# DM1097_PoE.net
KiCad netlist of a schematic drawn in Altium Designer
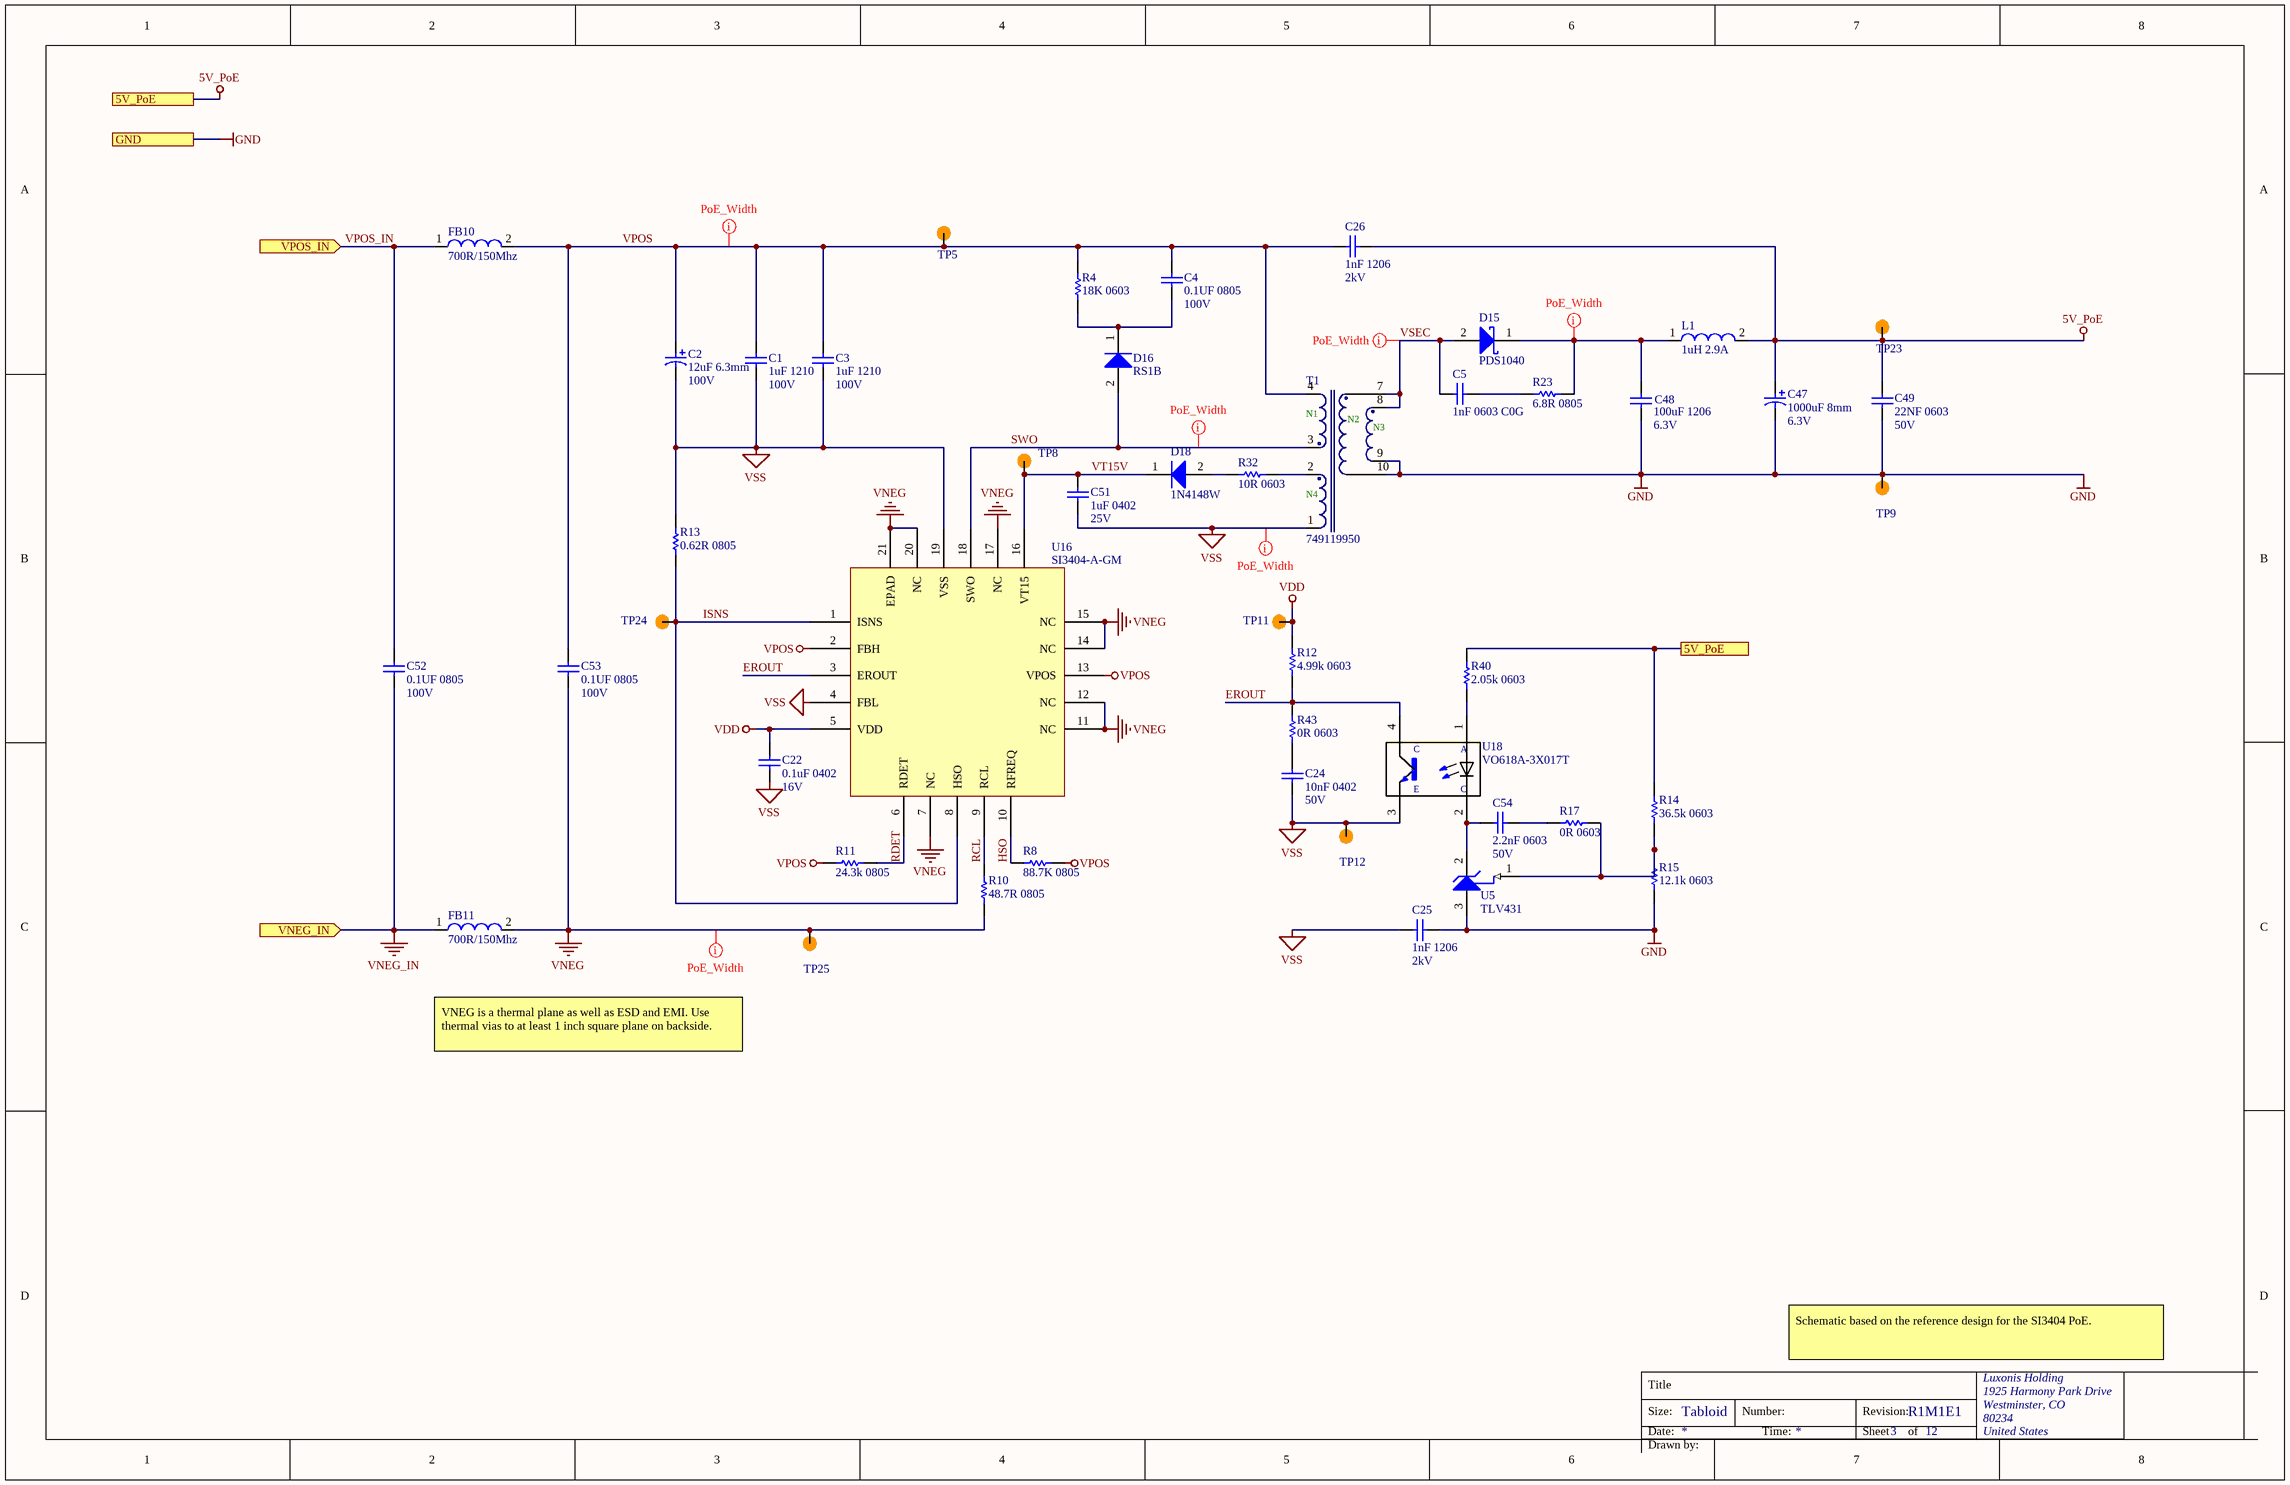
[diagram p0: DM1097_PoE.SchDoc]

(export (version "E")
  (design (tool "Eeschema 10.0.6"))
  (components
    (comp (ref "C1")
      (value "1uF 1210")
      (footprint "CAPC1210(3225)280_N")
      (description "CAP CER 1UF 100V X7R 1210")
      (fields (field (name "TOLERANCE") "10%") (field (name "VOLTAGE RATING") "100V"))
      (libsource (lib "PCBProject") (part "CL32B105KCJNNNE"))
    )
    (comp (ref "C2")
      (value "12uF 6.3mm")
      (footprint "EEU-FC2A120")
      (description "CAP ALUM 12UF 20% 100V RADIAL")
      (fields (field (name "TOLERANCE") "20%") (field (name "VOLTAGE") "100V"))
      (libsource (lib "BW2098POE") (part "EEU-FC2A120"))
    )
    (comp (ref "C3")
      (value "1uF 1210")
      (footprint "CAPC1210(3225)280_N")
      (description "CAP CER 1UF 100V X7R 1210")
      (fields (field (name "TOLERANCE") "10%") (field (name "VOLTAGE RATING") "100V"))
      (libsource (lib "PCBProject") (part "CL32B105KCJNNNE"))
    )
    (comp (ref "C4")
      (value "0.1UF 0805")
      (footprint "CAPC0805(2012)145_N")
      (description "CAP CER 0.1UF 100V X7R 0805")
      (fields (field (name "TOLERANCE") "10%") (field (name "VOLTAGE RATING") "100V"))
      (libsource (lib "BW2098POE") (part "CL21B104KCFNNNE"))
    )
    (comp (ref "C5")
      (value "1nF 0603 C0G")
      (footprint "CAP_Altium_Vault_Generic:CAPC0603(1608)100_N")
      (description "CAP CER 1000PF 50V C0G/NP0 0603")
      (fields
        (field (name "MANUFACTURER") "Murata")
        (field (name "MANUFACTURER PART NUMBER") "GRM1885C1H102FA01D")
      )
      (libsource (lib "LuxonisMaster") (part "GRM1885C1H102FA01D"))
    )
    (comp (ref "C22")
      (value "0.1uF 0402")
      (footprint "CAPC0402(1005)60_N")
      (description "CAP CER 0.1UF 16V X7R 0402")
      (fields (field (name "TOLERANCE") "10%") (field (name "VOLTAGE RATING") "16V"))
      (libsource (lib "PCBProject") (part "CL05B104KO5NFNC"))
    )
    (comp (ref "C24")
      (value "10nF 0402")
      (footprint "CAP_Altium_Vault_Generic:CAPC0402(1005)60_N")
      (description "CAP CER 10000PF 50V X7R 0402")
      (fields
        (field (name "TOLERANCE") "10%")
        (field (name "VOLTAGE") "25V")
        (field (name "VOLTAGE RATING") "50V")
      )
      (libsource (lib "LuxonisMaster") (part "GRM155R71H103KA88D"))
    )
    (comp (ref "C25")
      (value "1nF 1206")
      (footprint "CAPC1206(3216)190_N")
      (description "CAP CER 1000PF 2KV X7R 1206")
      (fields (field (name "TOLERANCE") "10%") (field (name "VOLTAGE RATING (DC)") "2kV"))
      (libsource (lib "PCBProject") (part "C1206C102KGRACTU"))
    )
    (comp (ref "C26")
      (value "1nF 1206")
      (footprint "CAPC1206(3216)190_N")
      (description "CAP CER 1000PF 2KV X7R 1206")
      (fields (field (name "TOLERANCE") "10%") (field (name "VOLTAGE RATING (DC)") "2kV"))
      (libsource (lib "PCBProject") (part "C1206C102KGRACTU"))
    )
    (comp (ref "C47")
      (value "1000uF 8mm")
      (footprint "ECA-0JM102")
      (description "CAP ALUM 1000UF 20% 6.3V RADIAL")
      (fields (field (name "TOLERANCE") "20%") (field (name "VOLTAGE") "6.3V"))
      (libsource (lib "BW2098POE") (part "ECA-0JM102"))
    )
    (comp (ref "C48")
      (value "100uF 1206")
      (footprint "CAPC1206(3216)190_N")
      (description "CAP CER 100UF 6.3V X5R 1206")
      (fields (field (name "TOLERANCE") "20%") (field (name "VOLTAGE") "6.3V"))
      (libsource (lib "PCBProject") (part "CL31A107MQHNNNE"))
    )
    (comp (ref "C49")
      (value "22NF 0603")
      (footprint "CAP_Altium_Vault_Generic:CAPC0603(1608)100_N")
      (description "CAP CER 0.022UF 50V X7R 0603")
      (fields (field (name "TOLERANCE") "10%") (field (name "VOLTAGE") "50V"))
      (libsource (lib "LuxonisMaster") (part "C0603C223K5RACTU"))
    )
    (comp (ref "C51")
      (value "1uF 0402")
      (footprint "CAP_Altium_Vault_Generic:CAPC0402(1005)70_N")
      (description "CAP CER 1UF 25V X5R 0402 10%")
      (fields
        (field (name "TOLERANCE") "10%")
        (field (name "VOLTAGE") "25V")
        (field (name "VOLTAGE RATING") "25V")
      )
      (libsource (lib "LuxonisMaster") (part "GRM155R61E105KA12D"))
    )
    (comp (ref "C52")
      (value "0.1UF 0805")
      (footprint "CAPC0805(2012)145_N")
      (description "CAP CER 0.1UF 100V X7R 0805")
      (fields (field (name "TOLERANCE") "10%") (field (name "VOLTAGE RATING") "100V"))
      (libsource (lib "PCBProject") (part "CL21B104KCFNNNE"))
    )
    (comp (ref "C53")
      (value "0.1UF 0805")
      (footprint "CAPC0805(2012)145_N")
      (description "CAP CER 0.1UF 100V X7R 0805")
      (fields (field (name "TOLERANCE") "10%") (field (name "VOLTAGE RATING") "100V"))
      (libsource (lib "PCBProject") (part "CL21B104KCFNNNE"))
    )
    (comp (ref "C54")
      (value "2.2nF 0603")
      (footprint "CAPC0603(1608)100_N")
      (description "CAP CER 2200PF 50V C0G/NP0 0603")
      (fields (field (name "TOLERANCE") "5%") (field (name "VOLTAGE") "50V"))
      (libsource (lib "BW2098POE") (part "GRM1885C1H222JA01D"))
    )
    (comp (ref "D15")
      (value "PDS1040")
      (footprint "PDS1040-13")
      (description "DIODE SCHOTTKY 40V 10A POWERDI5")
      (libsource (lib "PCBProject") (part "PDS1040-13"))
    )
    (comp (ref "D16")
      (value "RS1B")
      (footprint "RS1B")
      (description "DIODE GEN PURP 100V 1A SMA")
      (libsource (lib "BW2098POE") (part "RS1B"))
    )
    (comp (ref "D18")
      (value "1N4148W")
      (footprint "1N4148W-7-F")
      (description "DIODE GEN PURP 100V 300MA SOD123")
      (fields (field (name "VOLTAGE") "100V"))
      (libsource (lib "PCBProject") (part "1N4148W-7-F"))
    )
    (comp (ref "FB10")
      (value "700R/150Mhz")
      (footprint "742792040")
      (description "FERRITE BEAD 600 OHM 0805 1LN")
      (fields (field (name "TOLERANCE") "25%"))
      (libsource (lib "BW2098POE") (part "742792040"))
    )
    (comp (ref "FB11")
      (value "700R/150Mhz")
      (footprint "742792040")
      (description "FERRITE BEAD 600 OHM 0805 1LN")
      (fields (field (name "TOLERANCE") "25%"))
      (libsource (lib "BW2098POE") (part "742792040"))
    )
    (comp (ref "L1")
      (value "1uH 2.9A")
      (footprint "DO1608C-102MLx")
      (description "IND POWER WIREWOUND 1uH 20% 100KHz FERRITE 2.7A")
      (fields (field (name "TOLERANCE") "20%"))
      (libsource (lib "PCBProject") (part "DO1608C-102ML"))
    )
    (comp (ref "R4")
      (value "18K 0603")
      (footprint "RESC0603(1608)_N")
      (description "RES SMD 18K OHM 5% 1/10W 0603")
      (fields (field (name "TOLERANCE") "5%"))
      (libsource (lib "BW2098POE") (part "RC0603JR-0718KL"))
    )
    (comp (ref "R8")
      (value "88.7K 0805")
      (footprint "RESC0805(2012)_N")
      (description "RES SMD 88.7K OHM 1% 1/8W 0805")
      (fields (field (name "TOLERANCE") "1%"))
      (libsource (lib "BW2098POE") (part "CRCW080588K7FKEA"))
    )
    (comp (ref "R10")
      (value "48.7R 0805")
      (footprint "RESC0805(2012)_N")
      (description "RES SMD 48.7 OHM 1% 1/8W 0805")
      (fields (field (name "TOLERANCE") "1%"))
      (libsource (lib "PCBProject") (part "RC0805FR-0748R7L"))
    )
    (comp (ref "R11")
      (value "24.3k 0805")
      (footprint "RESC0805(2012)_N")
      (description "RES SMD 24.3K OHM 1% 1/8W 0805")
      (fields (field (name "TOLERANCE") "1%"))
      (libsource (lib "PCBProject") (part "CRCW080524K3FKEA"))
    )
    (comp (ref "R12")
      (value "4.99k 0603")
      (footprint "RESC0603(1608)_N")
      (description "RES SMD 4.99K OHM 1% 1/10W 0603")
      (fields (field (name "TOLERANCE") "1%"))
      (libsource (lib "PCBProject") (part "RC0603FR-074K99L"))
    )
    (comp (ref "R13")
      (value "0.62R 0805")
      (footprint "RESC0805(2012)_N")
      (description "RES SMD 620 MOHM 1% 1/8W 0805")
      (fields (field (name "TOLERANCE") "1%"))
      (libsource (lib "BW2098POE") (part "RL0805FR-070R62L"))
    )
    (comp (ref "R14")
      (value "36.5k 0603")
      (footprint "RESC0603(1608)_N")
      (description "RES SMD 36.5K OHM 1% 1/10W 0603")
      (fields (field (name "TOLERANCE") "1%"))
      (libsource (lib "PCBProject") (part "RC0603FR-0736K5L"))
    )
    (comp (ref "R15")
      (value "12.1k 0603")
      (footprint "RESC0603(1608)_N")
      (description "RES SMD 12.1K OHM 1% 1/10W 0603")
      (fields (field (name "TOLERANCE") "1%"))
      (libsource (lib "PCBProject") (part "RC0603FR-0712K1L"))
    )
    (comp (ref "R17")
      (value "0R 0603")
      (footprint "RES_Altium_Vault_Generic:RESC0603(1608)_N")
      (fields (field (name "TOLERANCE") "5%"))
      (libsource (lib "LuxonisMaster") (part "CRCW06030000Z0EA"))
    )
    (comp (ref "R23")
      (value "6.8R 0805")
      (footprint "RESC0805(2012)_N")
      (description "RES SMD 6.8 OHM 1% 1/8W 0805")
      (fields (field (name "TOLERANCE") "1%"))
      (libsource (lib "BW2098POE") (part "RC0805FR-076R8L"))
    )
    (comp (ref "R32")
      (value "10R 0603")
      (footprint "RESC0603(1608)_N")
      (description "RES SMD 10 OHM 1% 1/10W 0603")
      (fields (field (name "TOLERANCE") "1%"))
      (libsource (lib "PCBProject") (part "CRCW060310R0FKEA"))
    )
    (comp (ref "R40")
      (value "2.05k 0603")
      (footprint "RESC0603(1608)_N")
      (description "RES SMD 2.05K OHM 1% 1/10W 0603")
      (fields (field (name "TOLERANCE") "1%"))
      (libsource (lib "PCBProject") (part "RC0603FR-072K05L"))
    )
    (comp (ref "R43")
      (value "0R 0603")
      (footprint "RES_Altium_Vault_Generic:RESC0603(1608)_N")
      (fields (field (name "TOLERANCE") "5%"))
      (libsource (lib "LuxonisMaster") (part "CRCW06030000Z0EA"))
    )
    (comp (ref "T1")
      (value "749119950")
      (footprint "749119950")
      (description "TRANS FLYBACK POE 127UH SMD")
      (libsource (lib "BW2098POE") (part "749119950"))
    )
    (comp (ref "TP5")
      (value "TP100_200_NS")
      (footprint "LuxonisMaster:TP100_200_NS")
      (libsource (lib "LuxonisMaster") (part "TEST_POINT"))
    )
    (comp (ref "TP8")
      (value "TP100_200_NS")
      (footprint "LuxonisMaster:TP100_200_NS")
      (libsource (lib "LuxonisMaster") (part "TEST_POINT"))
    )
    (comp (ref "TP9")
      (value "TP100_200_NS")
      (footprint "LuxonisMaster:TP100_200_NS")
      (libsource (lib "LuxonisMaster") (part "TEST_POINT"))
    )
    (comp (ref "TP11")
      (value "TP100_200_NS")
      (footprint "LuxonisMaster:TP100_200_NS")
      (libsource (lib "LuxonisMaster") (part "TEST_POINT"))
    )
    (comp (ref "TP12")
      (value "TP100_200_NS")
      (footprint "LuxonisMaster:TP100_200_NS")
      (libsource (lib "LuxonisMaster") (part "TEST_POINT"))
    )
    (comp (ref "TP23")
      (value "TP100_200_NS")
      (footprint "LuxonisMaster:TP100_200_NS")
      (libsource (lib "LuxonisMaster") (part "TEST_POINT"))
    )
    (comp (ref "TP24")
      (value "TP100_200_NS")
      (footprint "LuxonisMaster:TP100_200_NS")
      (libsource (lib "LuxonisMaster") (part "TEST_POINT"))
    )
    (comp (ref "TP25")
      (value "TP100_200_NS")
      (footprint "LuxonisMaster:TP100_200_NS")
      (libsource (lib "LuxonisMaster") (part "TEST_POINT"))
    )
    (comp (ref "U5")
      (value "TLV431")
      (footprint "TLV431BCDBZR")
      (description "IC VREF SHUNT ADJ SOT23-3")
      (fields (field (name "TOLERANCE") "0.5%"))
      (libsource (lib "BW2098POE") (part "TLV431BCDBZR"))
    )
    (comp (ref "U16")
      (value "SI3404-A-GM")
      (footprint "Si3404-A-GM")
      (description "IC POE CNTRL 1 CHANNEL 20QFN")
      (libsource (lib "BW2098POE") (part "SI3404-A-GM"))
    )
    (comp (ref "U18")
      (value "VO618A-3X017T")
      (footprint "VO618A-3X017T")
      (description "OPTOISOLATOR 5.3KV TRANS 4-SMD")
      (libsource (lib "BW2098POE") (part "VO618A-3X017T"))
    )
  )
  (nets
    (net (code "1") (name "/EROUT") (class "Default")
      (node (ref "R12") (pin "1") (pinfunction "1_1") (pintype "passive"))
      (node (ref "R43") (pin "2") (pinfunction "2_2") (pintype "passive"))
      (node (ref "U16") (pin "3") (pinfunction "EROUT_3") (pintype "passive"))
      (node (ref "U18") (pin "4") (pinfunction "CO_4") (pintype "passive"))
    )
    (net (code "2") (name "/HSO") (class "Default")
      (node (ref "R8") (pin "2") (pinfunction "2_2") (pintype "passive"))
      (node (ref "U16") (pin "10") (pinfunction "RFREQ_10") (pintype "passive"))
    )
    (net (code "3") (name "/ISNS") (class "Default")
      (node (ref "R13") (pin "1") (pinfunction "1_1") (pintype "passive"))
      (node (ref "TP24") (pin "1") (pintype "passive"))
      (node (ref "U16") (pin "1") (pinfunction "ISNS_1") (pintype "passive"))
      (node (ref "U16") (pin "8") (pinfunction "HSO_8") (pintype "passive"))
    )
    (net (code "4") (name "/RCL") (class "Default")
      (node (ref "R10") (pin "2") (pinfunction "2_2") (pintype "passive"))
      (node (ref "U16") (pin "9") (pinfunction "RCL_9") (pintype "passive"))
    )
    (net (code "5") (name "/RDET") (class "Default")
      (node (ref "R11") (pin "1") (pinfunction "1_1") (pintype "passive"))
      (node (ref "U16") (pin "6") (pinfunction "RDET_6") (pintype "passive"))
    )
    (net (code "6") (name "/SWO") (class "Default")
      (node (ref "D16") (pin "2") (pinfunction "A_2") (pintype "passive"))
      (node (ref "T1") (pin "3") (pinfunction "3_3") (pintype "passive"))
      (node (ref "U16") (pin "18") (pinfunction "SWO_18") (pintype "passive"))
    )
    (net (code "7") (name "/VPOS_IN") (class "Default")
      (node (ref "C52") (pin "2") (pinfunction "2_2") (pintype "passive"))
      (node (ref "FB10") (pin "1") (pinfunction "1_1") (pintype "passive"))
    )
    (net (code "8") (name "/VSEC") (class "Default")
      (node (ref "C5") (pin "2") (pinfunction "2_2") (pintype "passive"))
      (node (ref "D15") (pin "2") (pinfunction "A_2") (pintype "passive"))
      (node (ref "T1") (pin "7") (pinfunction "7_7") (pintype "passive"))
      (node (ref "T1") (pin "8") (pinfunction "8_8") (pintype "passive"))
    )
    (net (code "9") (name "/VT15V") (class "Default")
      (node (ref "C51") (pin "2") (pinfunction "2_2") (pintype "passive"))
      (node (ref "D18") (pin "1") (pinfunction "K_1") (pintype "passive"))
      (node (ref "TP8") (pin "1") (pintype "passive"))
      (node (ref "U16") (pin "16") (pinfunction "VT15_16") (pintype "passive"))
    )
    (net (code "10") (name "5V_PoE") (class "Default")
      (node (ref "C26") (pin "2") (pinfunction "2_2") (pintype "passive"))
      (node (ref "C47") (pin "1") (pinfunction "1_1") (pintype "passive"))
      (node (ref "C49") (pin "2") (pinfunction "2_2") (pintype "passive"))
      (node (ref "L1") (pin "2") (pinfunction "2_2") (pintype "passive"))
      (node (ref "R14") (pin "2") (pinfunction "2_2") (pintype "passive"))
      (node (ref "R40") (pin "2") (pinfunction "2_2") (pintype "passive"))
      (node (ref "TP23") (pin "1") (pintype "passive"))
    )
    (net (code "11") (name "GND") (class "Default")
      (node (ref "C25") (pin "2") (pinfunction "2_2") (pintype "passive"))
      (node (ref "C47") (pin "2") (pinfunction "2_2") (pintype "passive"))
      (node (ref "C48") (pin "1") (pinfunction "1_1") (pintype "passive"))
      (node (ref "C49") (pin "1") (pinfunction "1_1") (pintype "passive"))
      (node (ref "R15") (pin "1") (pinfunction "1_1") (pintype "passive"))
      (node (ref "T1") (pin "10") (pinfunction "10_10") (pintype "passive"))
      (node (ref "T1") (pin "9") (pinfunction "9_9") (pintype "passive"))
      (node (ref "TP9") (pin "1") (pintype "passive"))
      (node (ref "U5") (pin "3") (pinfunction "ANODE_3") (pintype "passive"))
    )
    (net (code "12") (name "Net-(C5-Pad1)") (class "Default")
      (node (ref "C5") (pin "1") (pinfunction "1_1") (pintype "passive"))
      (node (ref "R23") (pin "1") (pinfunction "1_1") (pintype "passive"))
    )
    (net (code "13") (name "Net-(C24-Pad2)") (class "Default")
      (node (ref "C24") (pin "2") (pinfunction "2_2") (pintype "passive"))
      (node (ref "R43") (pin "1") (pinfunction "1_1") (pintype "passive"))
    )
    (net (code "14") (name "Net-(C54-Pad2)") (class "Default")
      (node (ref "C54") (pin "2") (pinfunction "2_2") (pintype "passive"))
      (node (ref "R17") (pin "2") (pinfunction "2_2") (pintype "passive"))
    )
    (net (code "15") (name "Net-(D15-K)") (class "Default")
      (node (ref "C48") (pin "2") (pinfunction "2_2") (pintype "passive"))
      (node (ref "D15") (pin "1") (pinfunction "K_1") (pintype "passive"))
      (node (ref "L1") (pin "1") (pinfunction "1_1") (pintype "passive"))
      (node (ref "R23") (pin "2") (pinfunction "2_2") (pintype "passive"))
    )
    (net (code "16") (name "Net-(D16-K)") (class "Default")
      (node (ref "C4") (pin "1") (pinfunction "1_1") (pintype "passive"))
      (node (ref "D16") (pin "1") (pinfunction "K_1") (pintype "passive"))
      (node (ref "R4") (pin "1") (pinfunction "1_1") (pintype "passive"))
    )
    (net (code "17") (name "Net-(D18-A)") (class "Default")
      (node (ref "D18") (pin "2") (pinfunction "A_2") (pintype "passive"))
      (node (ref "R32") (pin "1") (pinfunction "1_1") (pintype "passive"))
    )
    (net (code "18") (name "Net-(R32-Pad2)") (class "Default")
      (node (ref "R32") (pin "2") (pinfunction "2_2") (pintype "passive"))
      (node (ref "T1") (pin "2") (pinfunction "2_2") (pintype "passive"))
    )
    (net (code "19") (name "Net-(U5-REF)") (class "Default")
      (node (ref "R14") (pin "1") (pinfunction "1_1") (pintype "passive"))
      (node (ref "R15") (pin "2") (pinfunction "2_2") (pintype "passive"))
      (node (ref "R17") (pin "1") (pinfunction "1_1") (pintype "passive"))
      (node (ref "U5") (pin "1") (pinfunction "REF_1") (pintype "input"))
    )
    (net (code "20") (name "Net-(U18-A)") (class "Default")
      (node (ref "R40") (pin "1") (pinfunction "1_1") (pintype "passive"))
      (node (ref "U18") (pin "1") (pinfunction "A_1") (pintype "passive"))
    )
    (net (code "21") (name "Net-(U18-C)") (class "Default")
      (node (ref "C54") (pin "1") (pinfunction "1_1") (pintype "passive"))
      (node (ref "U18") (pin "2") (pinfunction "C_2") (pintype "passive"))
      (node (ref "U5") (pin "2") (pinfunction "CATHODE_2") (pintype "passive"))
    )
    (net (code "22") (name "VDD") (class "Default")
      (node (ref "C22") (pin "2") (pinfunction "2_2") (pintype "passive"))
      (node (ref "R12") (pin "2") (pinfunction "2_2") (pintype "passive"))
      (node (ref "TP11") (pin "1") (pintype "passive"))
      (node (ref "U16") (pin "5") (pinfunction "VDD_5") (pintype "passive"))
    )
    (net (code "23") (name "VNEG") (class "Default")
      (node (ref "C53") (pin "1") (pinfunction "1_1") (pintype "passive"))
      (node (ref "FB11") (pin "2") (pinfunction "2_2") (pintype "passive"))
      (node (ref "R10") (pin "1") (pinfunction "1_1") (pintype "passive"))
      (node (ref "TP25") (pin "1") (pintype "passive"))
      (node (ref "U16") (pin "11") (pinfunction "NC_11") (pintype "passive"))
      (node (ref "U16") (pin "12") (pinfunction "NC_12") (pintype "passive"))
      (node (ref "U16") (pin "14") (pinfunction "NC_14") (pintype "passive"))
      (node (ref "U16") (pin "15") (pinfunction "NC_15") (pintype "passive"))
      (node (ref "U16") (pin "17") (pinfunction "NC_17") (pintype "passive"))
      (node (ref "U16") (pin "20") (pinfunction "NC_20") (pintype "passive"))
      (node (ref "U16") (pin "21") (pinfunction "EPAD_21") (pintype "passive"))
      (node (ref "U16") (pin "7") (pinfunction "NC_7") (pintype "passive"))
    )
    (net (code "24") (name "VNEG_IN") (class "Default")
      (node (ref "C52") (pin "1") (pinfunction "1_1") (pintype "passive"))
      (node (ref "FB11") (pin "1") (pinfunction "1_1") (pintype "passive"))
    )
    (net (code "25") (name "VPOS") (class "Default")
      (node (ref "C1") (pin "2") (pinfunction "2_2") (pintype "passive"))
      (node (ref "C2") (pin "1") (pinfunction "1_1") (pintype "passive"))
      (node (ref "C26") (pin "1") (pinfunction "1_1") (pintype "passive"))
      (node (ref "C3") (pin "2") (pinfunction "2_2") (pintype "passive"))
      (node (ref "C4") (pin "2") (pinfunction "2_2") (pintype "passive"))
      (node (ref "C53") (pin "2") (pinfunction "2_2") (pintype "passive"))
      (node (ref "FB10") (pin "2") (pinfunction "2_2") (pintype "passive"))
      (node (ref "R11") (pin "2") (pinfunction "2_2") (pintype "passive"))
      (node (ref "R4") (pin "2") (pinfunction "2_2") (pintype "passive"))
      (node (ref "R8") (pin "1") (pinfunction "1_1") (pintype "passive"))
      (node (ref "T1") (pin "4") (pinfunction "4_4") (pintype "passive"))
      (node (ref "TP5") (pin "1") (pintype "passive"))
      (node (ref "U16") (pin "13") (pinfunction "VPOS_13") (pintype "passive"))
      (node (ref "U16") (pin "2") (pinfunction "FBH_2") (pintype "passive"))
    )
    (net (code "26") (name "VSS") (class "Default")
      (node (ref "C1") (pin "1") (pinfunction "1_1") (pintype "passive"))
      (node (ref "C2") (pin "2") (pinfunction "2_2") (pintype "passive"))
      (node (ref "C22") (pin "1") (pinfunction "1_1") (pintype "passive"))
      (node (ref "C24") (pin "1") (pinfunction "1_1") (pintype "passive"))
      (node (ref "C25") (pin "1") (pinfunction "1_1") (pintype "passive"))
      (node (ref "C3") (pin "1") (pinfunction "1_1") (pintype "passive"))
      (node (ref "C51") (pin "1") (pinfunction "1_1") (pintype "passive"))
      (node (ref "R13") (pin "2") (pinfunction "2_2") (pintype "passive"))
      (node (ref "T1") (pin "1") (pinfunction "1_1") (pintype "passive"))
      (node (ref "TP12") (pin "1") (pintype "passive"))
      (node (ref "U16") (pin "19") (pinfunction "VSS_19") (pintype "passive"))
      (node (ref "U16") (pin "4") (pinfunction "FBL_4") (pintype "passive"))
      (node (ref "U18") (pin "3") (pinfunction "E_3") (pintype "passive"))
    )
  )
)
